# adsr.net
KiCad netlist of a schematic drawn in EAGLE
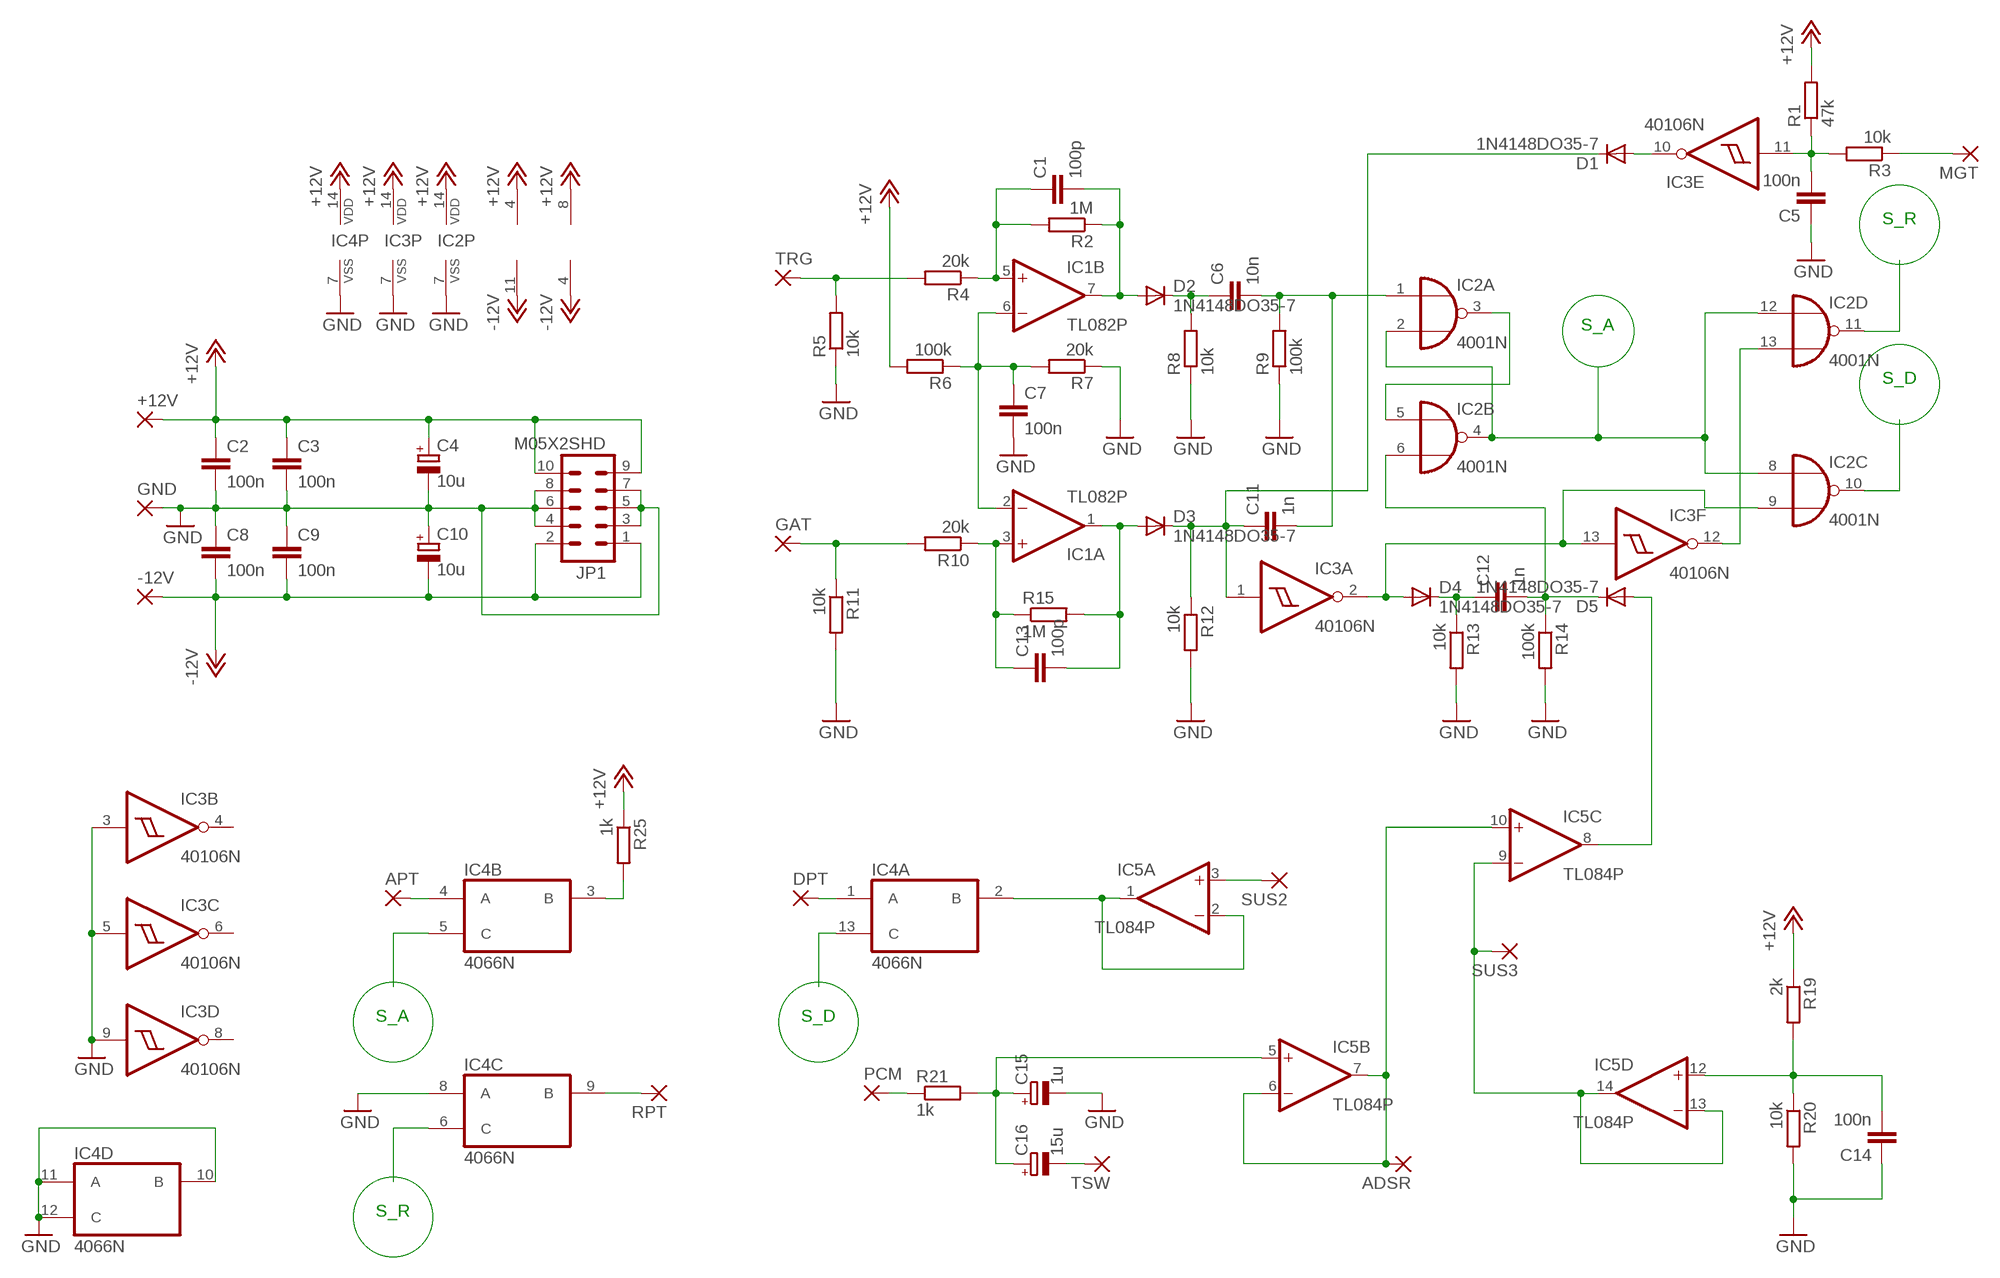
[diagram p0: schematic, sheet 1]

(export (version "E")
  (design (tool "Eeschema 10.0.6"))
  (components
    (comp (ref "+12V")
      (value "2,54/1,0")
      (footprint "eagle-import:2,54_1,0")
      (libsource (lib "eagle-import") (part "2,54/1,0"))
    )
    (comp (ref "-12V")
      (value "2,54/1,0")
      (footprint "eagle-import:2,54_1,0")
      (libsource (lib "eagle-import") (part "2,54/1,0"))
    )
    (comp (ref "ADSR")
      (value "2,54/1,0")
      (footprint "eagle-import:2,54_1,0")
      (libsource (lib "eagle-import") (part "2,54/1,0"))
    )
    (comp (ref "APT")
      (value "2,54/1,0")
      (footprint "eagle-import:2,54_1,0")
      (libsource (lib "eagle-import") (part "2,54/1,0"))
    )
    (comp (ref "C1")
      (value "100p")
      (footprint "eagle-import:C050-035X075")
      (libsource (lib "eagle-import") (part "C-EU050-035X075"))
    )
    (comp (ref "C2")
      (value "100n")
      (footprint "eagle-import:C050-035X075")
      (libsource (lib "eagle-import") (part "C-EU050-035X075"))
    )
    (comp (ref "C3")
      (value "100n")
      (footprint "eagle-import:C050-035X075")
      (libsource (lib "eagle-import") (part "C-EU050-035X075"))
    )
    (comp (ref "C4")
      (value "10u")
      (footprint "eagle-import:E3,5-8")
      (libsource (lib "eagle-import") (part "CPOL-EUE3.5-8"))
    )
    (comp (ref "C5")
      (value "100n")
      (footprint "eagle-import:C050-035X075")
      (libsource (lib "eagle-import") (part "C-EU050-035X075"))
    )
    (comp (ref "C6")
      (value "10n")
      (footprint "eagle-import:C050-035X075")
      (libsource (lib "eagle-import") (part "C-EU050-035X075"))
    )
    (comp (ref "C7")
      (value "100n")
      (footprint "eagle-import:C050-035X075")
      (libsource (lib "eagle-import") (part "C-EU050-035X075"))
    )
    (comp (ref "C8")
      (value "100n")
      (footprint "eagle-import:C050-035X075")
      (libsource (lib "eagle-import") (part "C-EU050-035X075"))
    )
    (comp (ref "C9")
      (value "100n")
      (footprint "eagle-import:C050-035X075")
      (libsource (lib "eagle-import") (part "C-EU050-035X075"))
    )
    (comp (ref "C10")
      (value "10u")
      (footprint "eagle-import:E3,5-8")
      (libsource (lib "eagle-import") (part "CPOL-EUE3.5-8"))
    )
    (comp (ref "C11")
      (value "1n")
      (footprint "eagle-import:C050-035X075")
      (libsource (lib "eagle-import") (part "C-EU050-035X075"))
    )
    (comp (ref "C12")
      (value "1n")
      (footprint "eagle-import:C050-035X075")
      (libsource (lib "eagle-import") (part "C-EU050-035X075"))
    )
    (comp (ref "C13")
      (value "100p")
      (footprint "eagle-import:C050-035X075")
      (libsource (lib "eagle-import") (part "C-EU050-035X075"))
    )
    (comp (ref "C14")
      (value "100n")
      (footprint "eagle-import:C050-035X075")
      (libsource (lib "eagle-import") (part "C-EU050-035X075"))
    )
    (comp (ref "C15")
      (value "1u")
      (footprint "eagle-import:E2,5-6")
      (libsource (lib "eagle-import") (part "CPOL-EUE2.5-6"))
    )
    (comp (ref "C16")
      (value "15u")
      (footprint "eagle-import:E3,5-8")
      (libsource (lib "eagle-import") (part "CPOL-EUE3.5-8"))
    )
    (comp (ref "D1")
      (value "1N4148DO35-7")
      (footprint "eagle-import:DO35-7")
      (libsource (lib "eagle-import") (part "1N4148DO35-7"))
    )
    (comp (ref "D2")
      (value "1N4148DO35-7")
      (footprint "eagle-import:DO35-7")
      (libsource (lib "eagle-import") (part "1N4148DO35-7"))
    )
    (comp (ref "D3")
      (value "1N4148DO35-7")
      (footprint "eagle-import:DO35-7")
      (libsource (lib "eagle-import") (part "1N4148DO35-7"))
    )
    (comp (ref "D4")
      (value "1N4148DO35-7")
      (footprint "eagle-import:DO35-7")
      (libsource (lib "eagle-import") (part "1N4148DO35-7"))
    )
    (comp (ref "D5")
      (value "1N4148DO35-7")
      (footprint "eagle-import:DO35-7")
      (libsource (lib "eagle-import") (part "1N4148DO35-7"))
    )
    (comp (ref "DPT")
      (value "2,54/1,0")
      (footprint "eagle-import:2,54_1,0")
      (libsource (lib "eagle-import") (part "2,54/1,0"))
    )
    (comp (ref "GAT")
      (value "2,54/1,0")
      (footprint "eagle-import:2,54_1,0")
      (libsource (lib "eagle-import") (part "2,54/1,0"))
    )
    (comp (ref "GND")
      (value "2,54/1,0")
      (footprint "eagle-import:2,54_1,0")
      (libsource (lib "eagle-import") (part "2,54/1,0"))
    )
    (comp (ref "IC1")
      (value "TL082P")
      (footprint "eagle-import:DIL08")
      (libsource (lib "eagle-import") (part "TL082P"))
    )
    (comp (ref "IC2")
      (value "4001N")
      (footprint "eagle-import:DIL14")
      (libsource (lib "eagle-import") (part "4001N"))
    )
    (comp (ref "IC3")
      (value "40106N")
      (footprint "eagle-import:DIL14")
      (libsource (lib "eagle-import") (part "40106N"))
    )
    (comp (ref "IC4")
      (value "4066N")
      (footprint "eagle-import:DIL14")
      (libsource (lib "eagle-import") (part "4066N"))
    )
    (comp (ref "IC5")
      (value "TL084P")
      (footprint "eagle-import:DIL14")
      (libsource (lib "eagle-import") (part "TL084P"))
    )
    (comp (ref "JP1")
      (value "M05X2SHD")
      (footprint "eagle-import:2X5-SHROUDED")
      (libsource (lib "eagle-import") (part "M05X2SHD"))
    )
    (comp (ref "MGT")
      (value "2,54/1,0")
      (footprint "eagle-import:2,54_1,0")
      (libsource (lib "eagle-import") (part "2,54/1,0"))
    )
    (comp (ref "PCM")
      (value "2,54/1,0")
      (footprint "eagle-import:2,54_1,0")
      (libsource (lib "eagle-import") (part "2,54/1,0"))
    )
    (comp (ref "R1")
      (value "47k")
      (footprint "eagle-import:0309_10")
      (libsource (lib "eagle-import") (part "R-EU_0309/10"))
    )
    (comp (ref "R2")
      (value "1M")
      (footprint "eagle-import:0309_10")
      (libsource (lib "eagle-import") (part "R-EU_0309/10"))
    )
    (comp (ref "R3")
      (value "10k")
      (footprint "eagle-import:0309_10")
      (libsource (lib "eagle-import") (part "R-EU_0309/10"))
    )
    (comp (ref "R4")
      (value "20k")
      (footprint "eagle-import:0309_10")
      (libsource (lib "eagle-import") (part "R-EU_0309/10"))
    )
    (comp (ref "R5")
      (value "10k")
      (footprint "eagle-import:0309_10")
      (libsource (lib "eagle-import") (part "R-EU_0309/10"))
    )
    (comp (ref "R6")
      (value "100k")
      (footprint "eagle-import:0309_10")
      (libsource (lib "eagle-import") (part "R-EU_0309/10"))
    )
    (comp (ref "R7")
      (value "20k")
      (footprint "eagle-import:0309_10")
      (libsource (lib "eagle-import") (part "R-EU_0309/10"))
    )
    (comp (ref "R8")
      (value "10k")
      (footprint "eagle-import:0309_10")
      (libsource (lib "eagle-import") (part "R-EU_0309/10"))
    )
    (comp (ref "R9")
      (value "100k")
      (footprint "eagle-import:0309_10")
      (libsource (lib "eagle-import") (part "R-EU_0309/10"))
    )
    (comp (ref "R10")
      (value "20k")
      (footprint "eagle-import:0309_10")
      (libsource (lib "eagle-import") (part "R-EU_0309/10"))
    )
    (comp (ref "R11")
      (value "10k")
      (footprint "eagle-import:0309_10")
      (libsource (lib "eagle-import") (part "R-EU_0309/10"))
    )
    (comp (ref "R12")
      (value "10k")
      (footprint "eagle-import:0309_10")
      (libsource (lib "eagle-import") (part "R-EU_0309/10"))
    )
    (comp (ref "R13")
      (value "10k")
      (footprint "eagle-import:0309_10")
      (libsource (lib "eagle-import") (part "R-EU_0309/10"))
    )
    (comp (ref "R14")
      (value "100k")
      (footprint "eagle-import:0309_10")
      (libsource (lib "eagle-import") (part "R-EU_0309/10"))
    )
    (comp (ref "R15")
      (value "1M")
      (footprint "eagle-import:0309_10")
      (libsource (lib "eagle-import") (part "R-EU_0309/10"))
    )
    (comp (ref "R19")
      (value "2k")
      (footprint "eagle-import:0309_10")
      (libsource (lib "eagle-import") (part "R-EU_0309/10"))
    )
    (comp (ref "R20")
      (value "10k")
      (footprint "eagle-import:0309_10")
      (libsource (lib "eagle-import") (part "R-EU_0309/10"))
    )
    (comp (ref "R21")
      (value "1k")
      (footprint "eagle-import:0309_10")
      (libsource (lib "eagle-import") (part "R-EU_0309/10"))
    )
    (comp (ref "R25")
      (value "1k")
      (footprint "eagle-import:0309_10")
      (libsource (lib "eagle-import") (part "R-EU_0309/10"))
    )
    (comp (ref "RPT")
      (value "2,54/1,0")
      (footprint "eagle-import:2,54_1,0")
      (libsource (lib "eagle-import") (part "2,54/1,0"))
    )
    (comp (ref "SUS2")
      (value "2,54/1,0")
      (footprint "eagle-import:2,54_1,0")
      (libsource (lib "eagle-import") (part "2,54/1,0"))
    )
    (comp (ref "SUS3")
      (value "2,54/1,0")
      (footprint "eagle-import:2,54_1,0")
      (libsource (lib "eagle-import") (part "2,54/1,0"))
    )
    (comp (ref "TRG")
      (value "2,54/1,0")
      (footprint "eagle-import:2,54_1,0")
      (libsource (lib "eagle-import") (part "2,54/1,0"))
    )
    (comp (ref "TSW")
      (value "2,54/1,0")
      (footprint "eagle-import:2,54_1,0")
      (libsource (lib "eagle-import") (part "2,54/1,0"))
    )
  )
  (nets
    (net (code "1") (name "+12V") (class "Default")
      (node (ref "+12V") (pin "1") (pinfunction "P_1") (pintype "passive"))
      (node (ref "C2") (pin "1") (pinfunction "1_1") (pintype "passive"))
      (node (ref "C3") (pin "1") (pinfunction "1_1") (pintype "passive"))
      (node (ref "C4") (pin "+") (pinfunction "+_+") (pintype "passive"))
      (node (ref "IC1") (pin "8") (pinfunction "V+_8") (pintype "power_in"))
      (node (ref "IC2") (pin "14") (pinfunction "VDD_14") (pintype "power_in"))
      (node (ref "IC3") (pin "14") (pinfunction "VDD_14") (pintype "power_in"))
      (node (ref "IC4") (pin "14") (pinfunction "VDD_14") (pintype "power_in"))
      (node (ref "IC5") (pin "4") (pinfunction "V+_4") (pintype "power_in"))
      (node (ref "JP1") (pin "10") (pinfunction "10_10") (pintype "passive"))
      (node (ref "JP1") (pin "9") (pinfunction "9_9") (pintype "passive"))
      (node (ref "R1") (pin "2") (pinfunction "2_2") (pintype "passive"))
      (node (ref "R19") (pin "1") (pinfunction "1_1") (pintype "passive"))
      (node (ref "R25") (pin "1") (pinfunction "1_1") (pintype "passive"))
      (node (ref "R6") (pin "2") (pinfunction "2_2") (pintype "passive"))
    )
    (net (code "2") (name "-12V") (class "Default")
      (node (ref "-12V") (pin "1") (pinfunction "P_1") (pintype "passive"))
      (node (ref "C10") (pin "-") (pinfunction "-_-") (pintype "passive"))
      (node (ref "C8") (pin "2") (pinfunction "2_2") (pintype "passive"))
      (node (ref "C9") (pin "2") (pinfunction "2_2") (pintype "passive"))
      (node (ref "IC1") (pin "4") (pinfunction "V-_4") (pintype "power_in"))
      (node (ref "IC5") (pin "11") (pinfunction "V-_11") (pintype "power_in"))
      (node (ref "JP1") (pin "1") (pinfunction "1_1") (pintype "passive"))
      (node (ref "JP1") (pin "2") (pinfunction "2_2") (pintype "passive"))
    )
    (net (code "3") (name "/S_A") (class "Default")
      (node (ref "IC2") (pin "12") (pinfunction "I0_12") (pintype "input"))
      (node (ref "IC2") (pin "2") (pinfunction "I1_2") (pintype "input"))
      (node (ref "IC2") (pin "4") (pinfunction "O_4") (pintype "output"))
      (node (ref "IC2") (pin "8") (pinfunction "I0_8") (pintype "input"))
      (node (ref "IC4") (pin "5") (pinfunction "C_5") (pintype "input"))
    )
    (net (code "4") (name "/S_D") (class "Default")
      (node (ref "IC2") (pin "10") (pinfunction "O_10") (pintype "output"))
      (node (ref "IC4") (pin "13") (pinfunction "C_13") (pintype "input"))
    )
    (net (code "5") (name "/S_R") (class "Default")
      (node (ref "IC2") (pin "11") (pinfunction "O_11") (pintype "output"))
      (node (ref "IC4") (pin "6") (pinfunction "C_6") (pintype "input"))
    )
    (net (code "6") (name "GND") (class "Default")
      (node (ref "C10") (pin "+") (pinfunction "+_+") (pintype "passive"))
      (node (ref "C14") (pin "1") (pinfunction "1_1") (pintype "passive"))
      (node (ref "C15") (pin "-") (pinfunction "-_-") (pintype "passive"))
      (node (ref "C2") (pin "2") (pinfunction "2_2") (pintype "passive"))
      (node (ref "C3") (pin "2") (pinfunction "2_2") (pintype "passive"))
      (node (ref "C4") (pin "-") (pinfunction "-_-") (pintype "passive"))
      (node (ref "C5") (pin "1") (pinfunction "1_1") (pintype "passive"))
      (node (ref "C7") (pin "2") (pinfunction "2_2") (pintype "passive"))
      (node (ref "C8") (pin "1") (pinfunction "1_1") (pintype "passive"))
      (node (ref "C9") (pin "1") (pinfunction "1_1") (pintype "passive"))
      (node (ref "GND") (pin "1") (pinfunction "P_1") (pintype "passive"))
      (node (ref "IC2") (pin "7") (pinfunction "VSS_7") (pintype "power_in"))
      (node (ref "IC3") (pin "3") (pinfunction "I_3") (pintype "input"))
      (node (ref "IC3") (pin "5") (pinfunction "I_5") (pintype "input"))
      (node (ref "IC3") (pin "7") (pinfunction "VSS_7") (pintype "power_in"))
      (node (ref "IC3") (pin "9") (pinfunction "I_9") (pintype "input"))
      (node (ref "IC4") (pin "10") (pinfunction "B_10") (pintype "tri_state"))
      (node (ref "IC4") (pin "11") (pinfunction "A_11") (pintype "tri_state"))
      (node (ref "IC4") (pin "12") (pinfunction "C_12") (pintype "input"))
      (node (ref "IC4") (pin "7") (pinfunction "VSS_7") (pintype "power_in"))
      (node (ref "IC4") (pin "8") (pinfunction "A_8") (pintype "tri_state"))
      (node (ref "JP1") (pin "3") (pinfunction "3_3") (pintype "passive"))
      (node (ref "JP1") (pin "4") (pinfunction "4_4") (pintype "passive"))
      (node (ref "JP1") (pin "5") (pinfunction "5_5") (pintype "passive"))
      (node (ref "JP1") (pin "6") (pinfunction "6_6") (pintype "passive"))
      (node (ref "JP1") (pin "7") (pinfunction "7_7") (pintype "passive"))
      (node (ref "JP1") (pin "8") (pinfunction "8_8") (pintype "passive"))
      (node (ref "R11") (pin "2") (pinfunction "2_2") (pintype "passive"))
      (node (ref "R12") (pin "2") (pinfunction "2_2") (pintype "passive"))
      (node (ref "R13") (pin "2") (pinfunction "2_2") (pintype "passive"))
      (node (ref "R14") (pin "2") (pinfunction "2_2") (pintype "passive"))
      (node (ref "R20") (pin "2") (pinfunction "2_2") (pintype "passive"))
      (node (ref "R5") (pin "1") (pinfunction "1_1") (pintype "passive"))
      (node (ref "R7") (pin "1") (pinfunction "1_1") (pintype "passive"))
      (node (ref "R8") (pin "1") (pinfunction "1_1") (pintype "passive"))
      (node (ref "R9") (pin "1") (pinfunction "1_1") (pintype "passive"))
    )
    (net (code "7") (name "Net-(ADSR-P)") (class "Default")
      (node (ref "ADSR") (pin "1") (pinfunction "P_1") (pintype "passive"))
      (node (ref "IC5") (pin "10") (pinfunction "+IN_10") (pintype "input"))
      (node (ref "IC5") (pin "6") (pinfunction "-IN_6") (pintype "input"))
      (node (ref "IC5") (pin "7") (pinfunction "OUT_7") (pintype "output"))
    )
    (net (code "8") (name "Net-(APT-P)") (class "Default")
      (node (ref "APT") (pin "1") (pinfunction "P_1") (pintype "passive"))
      (node (ref "IC4") (pin "4") (pinfunction "A_4") (pintype "tri_state"))
    )
    (net (code "9") (name "Net-(C6-Pad1)") (class "Default")
      (node (ref "C6") (pin "1") (pinfunction "1_1") (pintype "passive"))
      (node (ref "D2") (pin "C") (pinfunction "C_C") (pintype "passive"))
      (node (ref "R8") (pin "2") (pinfunction "2_2") (pintype "passive"))
    )
    (net (code "10") (name "Net-(C12-Pad1)") (class "Default")
      (node (ref "C12") (pin "1") (pinfunction "1_1") (pintype "passive"))
      (node (ref "D4") (pin "C") (pinfunction "C_C") (pintype "passive"))
      (node (ref "R13") (pin "1") (pinfunction "1_1") (pintype "passive"))
    )
    (net (code "11") (name "Net-(DPT-P)") (class "Default")
      (node (ref "DPT") (pin "1") (pinfunction "P_1") (pintype "passive"))
      (node (ref "IC4") (pin "1") (pinfunction "A_1") (pintype "tri_state"))
    )
    (net (code "12") (name "Net-(GAT-P)") (class "Default")
      (node (ref "GAT") (pin "1") (pinfunction "P_1") (pintype "passive"))
      (node (ref "R10") (pin "2") (pinfunction "2_2") (pintype "passive"))
      (node (ref "R11") (pin "1") (pinfunction "1_1") (pintype "passive"))
    )
    (net (code "13") (name "Net-(IC1A-+IN)") (class "Default")
      (node (ref "C13") (pin "1") (pinfunction "1_1") (pintype "passive"))
      (node (ref "IC1") (pin "3") (pinfunction "+IN_3") (pintype "input"))
      (node (ref "R10") (pin "1") (pinfunction "1_1") (pintype "passive"))
      (node (ref "R15") (pin "1") (pinfunction "1_1") (pintype "passive"))
    )
    (net (code "14") (name "Net-(IC1A--IN)") (class "Default")
      (node (ref "C7") (pin "1") (pinfunction "1_1") (pintype "passive"))
      (node (ref "IC1") (pin "2") (pinfunction "-IN_2") (pintype "input"))
      (node (ref "IC1") (pin "6") (pinfunction "-IN_6") (pintype "input"))
      (node (ref "R6") (pin "1") (pinfunction "1_1") (pintype "passive"))
      (node (ref "R7") (pin "2") (pinfunction "2_2") (pintype "passive"))
    )
    (net (code "15") (name "Net-(IC1A-OUT)") (class "Default")
      (node (ref "C13") (pin "2") (pinfunction "2_2") (pintype "passive"))
      (node (ref "D3") (pin "A") (pinfunction "A_A") (pintype "passive"))
      (node (ref "IC1") (pin "1") (pinfunction "OUT_1") (pintype "output"))
      (node (ref "R15") (pin "2") (pinfunction "2_2") (pintype "passive"))
    )
    (net (code "16") (name "Net-(IC1B-+IN)") (class "Default")
      (node (ref "C1") (pin "1") (pinfunction "1_1") (pintype "passive"))
      (node (ref "IC1") (pin "5") (pinfunction "+IN_5") (pintype "input"))
      (node (ref "R2") (pin "2") (pinfunction "2_2") (pintype "passive"))
      (node (ref "R4") (pin "1") (pinfunction "1_1") (pintype "passive"))
    )
    (net (code "17") (name "Net-(IC1B-OUT)") (class "Default")
      (node (ref "C1") (pin "2") (pinfunction "2_2") (pintype "passive"))
      (node (ref "D2") (pin "A") (pinfunction "A_A") (pintype "passive"))
      (node (ref "IC1") (pin "7") (pinfunction "OUT_7") (pintype "output"))
      (node (ref "R2") (pin "1") (pinfunction "1_1") (pintype "passive"))
    )
    (net (code "18") (name "Net-(IC2A-I0)") (class "Default")
      (node (ref "C11") (pin "2") (pinfunction "2_2") (pintype "passive"))
      (node (ref "C6") (pin "2") (pinfunction "2_2") (pintype "passive"))
      (node (ref "IC2") (pin "1") (pinfunction "I0_1") (pintype "input"))
      (node (ref "R9") (pin "2") (pinfunction "2_2") (pintype "passive"))
    )
    (net (code "19") (name "Net-(IC2A-O)") (class "Default")
      (node (ref "IC2") (pin "3") (pinfunction "O_3") (pintype "output"))
      (node (ref "IC2") (pin "5") (pinfunction "I0_5") (pintype "input"))
    )
    (net (code "20") (name "Net-(IC2B-I1)") (class "Default")
      (node (ref "C12") (pin "2") (pinfunction "2_2") (pintype "passive"))
      (node (ref "D5") (pin "C") (pinfunction "C_C") (pintype "passive"))
      (node (ref "IC2") (pin "6") (pinfunction "I1_6") (pintype "input"))
      (node (ref "R14") (pin "1") (pinfunction "1_1") (pintype "passive"))
    )
    (net (code "21") (name "Net-(IC2C-I1)") (class "Default")
      (node (ref "D4") (pin "A") (pinfunction "A_A") (pintype "passive"))
      (node (ref "IC2") (pin "9") (pinfunction "I1_9") (pintype "input"))
      (node (ref "IC3") (pin "13") (pinfunction "I_13") (pintype "input"))
      (node (ref "IC3") (pin "2") (pinfunction "O_2") (pintype "output"))
    )
    (net (code "22") (name "Net-(IC2D-I1)") (class "Default")
      (node (ref "IC2") (pin "13") (pinfunction "I1_13") (pintype "input"))
      (node (ref "IC3") (pin "12") (pinfunction "O_12") (pintype "output"))
    )
    (net (code "23") (name "Net-(IC3A-I)") (class "Default")
      (node (ref "C11") (pin "1") (pinfunction "1_1") (pintype "passive"))
      (node (ref "D1") (pin "C") (pinfunction "C_C") (pintype "passive"))
      (node (ref "D3") (pin "C") (pinfunction "C_C") (pintype "passive"))
      (node (ref "IC3") (pin "1") (pinfunction "I_1") (pintype "input"))
      (node (ref "R12") (pin "1") (pinfunction "1_1") (pintype "passive"))
    )
    (net (code "24") (name "Net-(IC3E-I)") (class "Default")
      (node (ref "C5") (pin "2") (pinfunction "2_2") (pintype "passive"))
      (node (ref "IC3") (pin "11") (pinfunction "I_11") (pintype "input"))
      (node (ref "R1") (pin "1") (pinfunction "1_1") (pintype "passive"))
      (node (ref "R3") (pin "2") (pinfunction "2_2") (pintype "passive"))
    )
    (net (code "25") (name "Net-(IC3E-O)") (class "Default")
      (node (ref "D1") (pin "A") (pinfunction "A_A") (pintype "passive"))
      (node (ref "IC3") (pin "10") (pinfunction "O_10") (pintype "output"))
    )
    (net (code "26") (name "Net-(IC4A-B)") (class "Default")
      (node (ref "IC4") (pin "2") (pinfunction "B_2") (pintype "tri_state"))
      (node (ref "IC5") (pin "1") (pinfunction "OUT_1") (pintype "output"))
      (node (ref "IC5") (pin "2") (pinfunction "-IN_2") (pintype "input"))
    )
    (net (code "27") (name "Net-(IC4B-B)") (class "Default")
      (node (ref "IC4") (pin "3") (pinfunction "B_3") (pintype "tri_state"))
      (node (ref "R25") (pin "2") (pinfunction "2_2") (pintype "passive"))
    )
    (net (code "28") (name "Net-(IC4C-B)") (class "Default")
      (node (ref "IC4") (pin "9") (pinfunction "B_9") (pintype "tri_state"))
      (node (ref "RPT") (pin "1") (pinfunction "P_1") (pintype "passive"))
    )
    (net (code "29") (name "Net-(IC5A-+IN)") (class "Default")
      (node (ref "IC5") (pin "3") (pinfunction "+IN_3") (pintype "input"))
      (node (ref "SUS2") (pin "1") (pinfunction "P_1") (pintype "passive"))
    )
    (net (code "30") (name "Net-(IC5B-+IN)") (class "Default")
      (node (ref "C15") (pin "+") (pinfunction "+_+") (pintype "passive"))
      (node (ref "C16") (pin "+") (pinfunction "+_+") (pintype "passive"))
      (node (ref "IC5") (pin "5") (pinfunction "+IN_5") (pintype "input"))
      (node (ref "R21") (pin "2") (pinfunction "2_2") (pintype "passive"))
    )
    (net (code "31") (name "Net-(IC5C--IN)") (class "Default")
      (node (ref "IC5") (pin "13") (pinfunction "-IN_13") (pintype "input"))
      (node (ref "IC5") (pin "14") (pinfunction "OUT_14") (pintype "output"))
      (node (ref "IC5") (pin "9") (pinfunction "-IN_9") (pintype "input"))
      (node (ref "SUS3") (pin "1") (pinfunction "P_1") (pintype "passive"))
    )
    (net (code "32") (name "Net-(IC5C-OUT)") (class "Default")
      (node (ref "D5") (pin "A") (pinfunction "A_A") (pintype "passive"))
      (node (ref "IC5") (pin "8") (pinfunction "OUT_8") (pintype "output"))
    )
    (net (code "33") (name "Net-(IC5D-+IN)") (class "Default")
      (node (ref "C14") (pin "2") (pinfunction "2_2") (pintype "passive"))
      (node (ref "IC5") (pin "12") (pinfunction "+IN_12") (pintype "input"))
      (node (ref "R19") (pin "2") (pinfunction "2_2") (pintype "passive"))
      (node (ref "R20") (pin "1") (pinfunction "1_1") (pintype "passive"))
    )
    (net (code "34") (name "Net-(MGT-P)") (class "Default")
      (node (ref "MGT") (pin "1") (pinfunction "P_1") (pintype "passive"))
      (node (ref "R3") (pin "1") (pinfunction "1_1") (pintype "passive"))
    )
    (net (code "35") (name "Net-(PCM-P)") (class "Default")
      (node (ref "PCM") (pin "1") (pinfunction "P_1") (pintype "passive"))
      (node (ref "R21") (pin "1") (pinfunction "1_1") (pintype "passive"))
    )
    (net (code "36") (name "Net-(TRG-P)") (class "Default")
      (node (ref "R4") (pin "2") (pinfunction "2_2") (pintype "passive"))
      (node (ref "R5") (pin "2") (pinfunction "2_2") (pintype "passive"))
      (node (ref "TRG") (pin "1") (pinfunction "P_1") (pintype "passive"))
    )
    (net (code "37") (name "Net-(TSW-P)") (class "Default")
      (node (ref "C16") (pin "-") (pinfunction "-_-") (pintype "passive"))
      (node (ref "TSW") (pin "1") (pinfunction "P_1") (pintype "passive"))
    )
    (net (code "38") (name "unconnected-(IC3B-O-Pad4)") (class "Default")
      (node (ref "IC3") (pin "4") (pinfunction "O_4") (pintype "output"))
    )
    (net (code "39") (name "unconnected-(IC3C-O-Pad6)") (class "Default")
      (node (ref "IC3") (pin "6") (pinfunction "O_6") (pintype "output"))
    )
    (net (code "40") (name "unconnected-(IC3D-O-Pad8)") (class "Default")
      (node (ref "IC3") (pin "8") (pinfunction "O_8") (pintype "output"))
    )
  )
)
